# wifi.net
KiCad netlist of a schematic drawn in Altium Designer
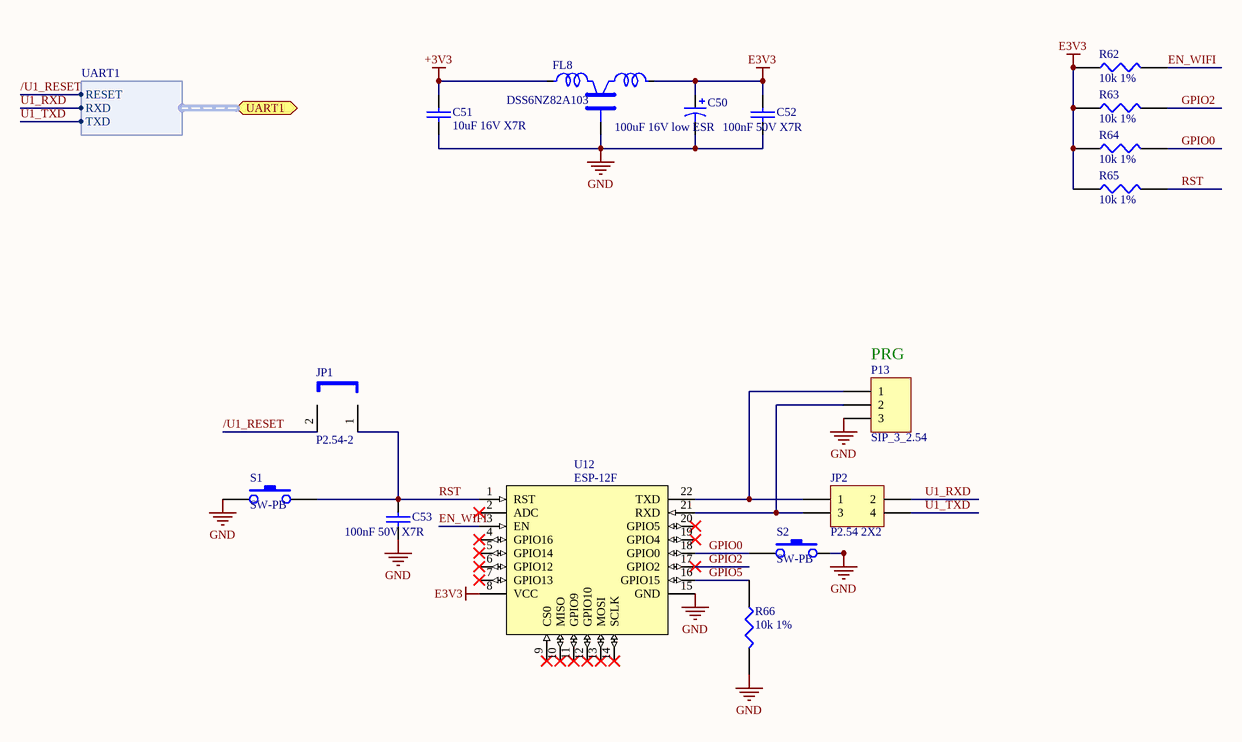
[diagram p0: wifi.SchDoc]

(export (version "E")
  (design (tool "Eeschema 10.0.6"))
  (components
    (comp (ref "C50")
      (value "100uF 16V low ESR")
      (footprint "Capacitor Polar Radial Cylinder:CAPPR2-5x11")
      (description "Polarized Capacitor (Radial)")
      (libsource (lib "Miscellaneous Devices") (part "Cap Pol1"))
    )
    (comp (ref "C51")
      (value "10uF 16V X7R")
      (footprint "IPC-7352 Chip_Capacitor_N:CAPC3216N")
      (libsource (lib "*") (part "CAP"))
    )
    (comp (ref "C52")
      (value "100nF 50V X7R")
      (footprint "IPC-7352 Chip_Capacitor_N:CAPC2012N")
      (libsource (lib "*") (part "CAP"))
    )
    (comp (ref "C53")
      (value "100nF 50V X7R")
      (footprint "IPC-7352 Chip_Capacitor_N:CAPC2012N")
      (libsource (lib "*") (part "CAP"))
    )
    (comp (ref "FL8")
      (value "DSS6NZ82A103")
      (footprint "UserPcbLib:DSS6")
      (description "Murata EMI suppression filter")
      (fields (field (name "MANUFACTURER") "Murata"))
      (libsource (lib "UserSchlib") (part "DSS6"))
    )
    (comp (ref "JP1")
      (value "P2.54-2")
      (footprint "UserPcbLib:JP2-P2.54")
      (description "Jumper")
      (libsource (lib "*") (part "JUMPER"))
    )
    (comp (ref "JP2")
      (value "P2.54 2X2")
      (footprint "HDR2X2")
      (description "Jumper 2.54 2-Pin, Dual row")
      (fields (field (name "PUBLISHER") "Altium Limited"))
      (libsource (lib "Miscellaneous Connectors") (part "Header 2X2"))
    )
    (comp (ref "P13")
      (value "SIP_3_2.54")
      (footprint "UserPcbLib:REAL_SIP3_2.54")
      (description "Header, 3-Pin")
      (fields (field (name "PUBLISHER") "Altium Limited"))
      (libsource (lib "Miscellaneous Connectors") (part "Header 3"))
    )
    (comp (ref "R62")
      (value "10k 1%")
      (footprint "IPC-7352 Chip_Resistor_N:RESC2012N")
      (libsource (lib "*") (part "RES1"))
    )
    (comp (ref "R63")
      (value "10k 1%")
      (footprint "IPC-7352 Chip_Resistor_N:RESC2012N")
      (libsource (lib "*") (part "RES1"))
    )
    (comp (ref "R64")
      (value "10k 1%")
      (footprint "IPC-7352 Chip_Resistor_N:RESC2012N")
      (libsource (lib "*") (part "RES1"))
    )
    (comp (ref "R65")
      (value "10k 1%")
      (footprint "IPC-7352 Chip_Resistor_N:RESC2012N")
      (libsource (lib "*") (part "RES1"))
    )
    (comp (ref "R66")
      (value "10k 1%")
      (footprint "IPC-7352 Chip_Resistor_N:RESC2012N")
      (libsource (lib "*") (part "RES1"))
    )
    (comp (ref "S1") (value "SW-PB") (footprint "SW5X7") (libsource (lib "*") (part "SW-PB")))
    (comp (ref "S2") (value "SW-PB") (footprint "SW5X7") (libsource (lib "*") (part "SW-PB")))
    (comp (ref "U12")
      (value "ESP-12F")
      (footprint "UserPcbLib:ESP-12F")
      (description "Wi-Fi module")
      (fields (field (name "MANUFACTURER") "Ai-Thinker"))
      (libsource (lib "UserSchlib") (part "ESP-12F"))
    )
  )
  (nets
    (net (code "2") (name "+3V3") (class "Default")
      (node (ref "C51") (pin "1") (pintype "passive"))
      (node (ref "FL8") (pin "1") (pinfunction "1_1") (pintype "power_in"))
    )
    (net (code "3") (name "/EN_WIFI") (class "Default")
      (node (ref "R62") (pin "2") (pinfunction "2_2") (pintype "passive"))
      (node (ref "U12") (pin "3") (pinfunction "EN_3") (pintype "input"))
    )
    (net (code "4") (name "/GPIO0") (class "Default")
      (node (ref "R64") (pin "2") (pinfunction "2_2") (pintype "passive"))
      (node (ref "S2") (pin "1") (pinfunction "1_1") (pintype "passive"))
      (node (ref "U12") (pin "18") (pinfunction "GPIO0_18") (pintype "bidirectional"))
    )
    (net (code "5") (name "/GPIO2") (class "Default")
      (node (ref "R63") (pin "2") (pinfunction "2_2") (pintype "passive"))
      (node (ref "U12") (pin "17") (pinfunction "GPIO2_17") (pintype "bidirectional"))
    )
    (net (code "6") (name "/GPIO5") (class "Default")
      (node (ref "R66") (pin "1") (pinfunction "1_1") (pintype "passive"))
      (node (ref "U12") (pin "16") (pinfunction "GPIO15_16") (pintype "bidirectional"))
    )
    (net (code "7") (name "/RST") (class "Default")
      (node (ref "C53") (pin "1") (pintype "passive"))
      (node (ref "JP1") (pin "1") (pinfunction "1_1") (pintype "passive"))
      (node (ref "R65") (pin "2") (pinfunction "2_2") (pintype "passive"))
      (node (ref "S1") (pin "2") (pinfunction "2_2") (pintype "passive"))
      (node (ref "U12") (pin "1") (pinfunction "RST_1") (pintype "input"))
    )
    (net (code "8") (name "/U1_RXD") (class "Default")
      (node (ref "JP2") (pin "2") (pinfunction "2_2") (pintype "passive"))
    )
    (net (code "9") (name "/U1_TXD") (class "Default")
      (node (ref "JP2") (pin "4") (pinfunction "4_4") (pintype "passive"))
    )
    (net (code "11") (name "/{slash}U1_RESET") (class "Default")
      (node (ref "JP1") (pin "2") (pinfunction "2_2") (pintype "passive"))
    )
    (net (code "12") (name "E3V3") (class "Default")
      (node (ref "C50") (pin "1") (pinfunction "1_1") (pintype "passive"))
      (node (ref "C52") (pin "1") (pintype "passive"))
      (node (ref "FL8") (pin "3") (pinfunction "3_3") (pintype "power_in"))
      (node (ref "R62") (pin "1") (pinfunction "1_1") (pintype "passive"))
      (node (ref "R63") (pin "1") (pinfunction "1_1") (pintype "passive"))
      (node (ref "R64") (pin "1") (pinfunction "1_1") (pintype "passive"))
      (node (ref "R65") (pin "1") (pinfunction "1_1") (pintype "passive"))
      (node (ref "U12") (pin "8") (pinfunction "VCC_8") (pintype "power_in"))
    )
    (net (code "13") (name "GND") (class "Default")
      (node (ref "C50") (pin "2") (pinfunction "2_2") (pintype "passive"))
      (node (ref "C51") (pin "2") (pintype "passive"))
      (node (ref "C52") (pin "2") (pintype "passive"))
      (node (ref "C53") (pin "2") (pintype "passive"))
      (node (ref "FL8") (pin "2") (pinfunction "2_2") (pintype "power_in"))
      (node (ref "P13") (pin "3") (pinfunction "3_3") (pintype "passive"))
      (node (ref "R66") (pin "2") (pinfunction "2_2") (pintype "passive"))
      (node (ref "S1") (pin "1") (pinfunction "1_1") (pintype "passive"))
      (node (ref "S2") (pin "2") (pinfunction "2_2") (pintype "passive"))
      (node (ref "U12") (pin "15") (pinfunction "GND_15") (pintype "power_in"))
    )
    (net (code "14") (name "Net-(U12-RXD)") (class "Default")
      (node (ref "JP2") (pin "3") (pinfunction "3_3") (pintype "passive"))
      (node (ref "P13") (pin "2") (pinfunction "2_2") (pintype "passive"))
      (node (ref "U12") (pin "21") (pinfunction "RXD_21") (pintype "input"))
    )
    (net (code "15") (name "Net-(U12-TXD)") (class "Default")
      (node (ref "JP2") (pin "1") (pinfunction "1_1") (pintype "passive"))
      (node (ref "P13") (pin "1") (pinfunction "1_1") (pintype "passive"))
      (node (ref "U12") (pin "22") (pinfunction "TXD_22") (pintype "tri_state"))
    )
    (net (code "16") (name "unconnected-(U12-ADC-Pad2)") (class "Default")
      (node (ref "U12") (pin "2") (pinfunction "ADC_2") (pintype "passive+no_connect"))
    )
    (net (code "17") (name "unconnected-(U12-CS0-Pad9)") (class "Default")
      (node (ref "U12") (pin "9") (pinfunction "CS0_9") (pintype "input+no_connect"))
    )
    (net (code "18") (name "unconnected-(U12-GPIO4-Pad19)") (class "Default")
      (node (ref "U12") (pin "19") (pinfunction "GPIO4_19") (pintype "bidirectional+no_connect"))
    )
    (net (code "19") (name "unconnected-(U12-GPIO5-Pad20)") (class "Default")
      (node (ref "U12") (pin "20") (pinfunction "GPIO5_20") (pintype "bidirectional+no_connect"))
    )
    (net (code "20") (name "unconnected-(U12-GPIO9-Pad11)") (class "Default")
      (node (ref "U12") (pin "11") (pinfunction "GPIO9_11") (pintype "bidirectional+no_connect"))
    )
    (net (code "21") (name "unconnected-(U12-GPIO10-Pad12)") (class "Default")
      (node (ref "U12") (pin "12") (pinfunction "GPIO10_12") (pintype "bidirectional+no_connect"))
    )
    (net (code "22") (name "unconnected-(U12-GPIO12-Pad6)") (class "Default")
      (node (ref "U12") (pin "6") (pinfunction "GPIO12_6") (pintype "bidirectional+no_connect"))
    )
    (net (code "23") (name "unconnected-(U12-GPIO13-Pad7)") (class "Default")
      (node (ref "U12") (pin "7") (pinfunction "GPIO13_7") (pintype "bidirectional+no_connect"))
    )
    (net (code "24") (name "unconnected-(U12-GPIO14-Pad5)") (class "Default")
      (node (ref "U12") (pin "5") (pinfunction "GPIO14_5") (pintype "bidirectional+no_connect"))
    )
    (net (code "25") (name "unconnected-(U12-GPIO16-Pad4)") (class "Default")
      (node (ref "U12") (pin "4") (pinfunction "GPIO16_4") (pintype "bidirectional+no_connect"))
    )
    (net (code "26") (name "unconnected-(U12-MISO-Pad10)") (class "Default")
      (node (ref "U12") (pin "10") (pinfunction "MISO_10") (pintype "bidirectional+no_connect"))
    )
    (net (code "27") (name "unconnected-(U12-MOSI-Pad13)") (class "Default")
      (node (ref "U12") (pin "13") (pinfunction "MOSI_13") (pintype "bidirectional+no_connect"))
    )
    (net (code "28") (name "unconnected-(U12-SCLK-Pad14)") (class "Default")
      (node (ref "U12") (pin "14") (pinfunction "SCLK_14") (pintype "bidirectional+no_connect"))
    )
  )
)
